# SPK_P.net
KiCad netlist of a schematic drawn in Altium Designer
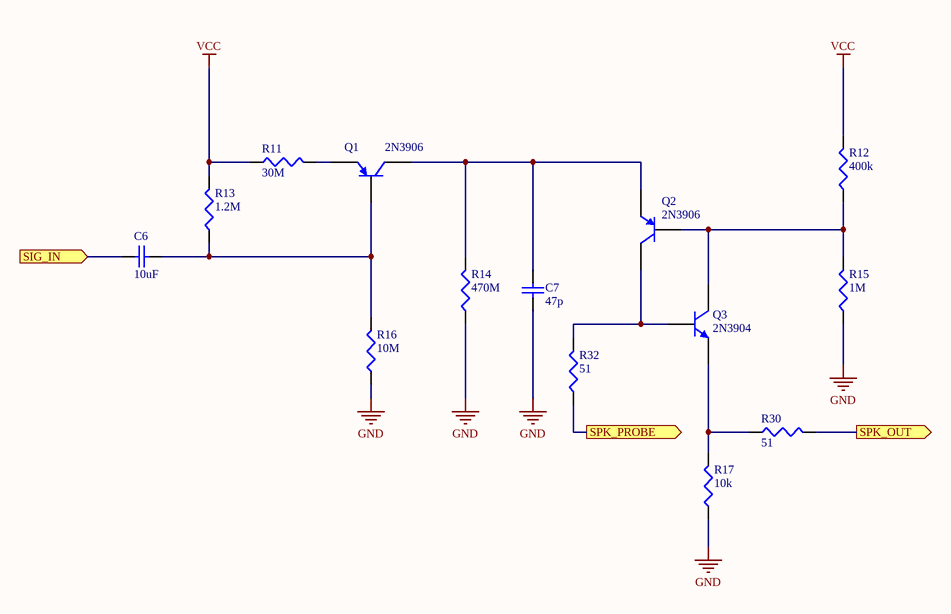
[diagram p0: SPK_P.SchDoc]

(export (version "E")
  (design (tool "Eeschema 10.0.6"))
  (components
    (comp (ref "C6")
      (value "10uF")
      (footprint "SMD-0603")
      (description "Ceramic Capacitor 0603")
      (libsource (lib "LCR") (part "CAP0603"))
    )
    (comp (ref "C7")
      (value "47p")
      (footprint "SMD-0603")
      (description "Ceramic Capacitor 0603")
      (libsource (lib "LCR") (part "CAP0603"))
    )
    (comp (ref "Q1")
      (value "2N3906")
      (footprint "TO-92A")
      (description "PNP General Purpose Amplifier")
      (fields (field (name "PUBLISHER") "Altium Limited"))
      (libsource (lib "Miscellaneous Devices") (part "2N3906"))
    )
    (comp (ref "Q2")
      (value "2N3906")
      (footprint "TO-92A")
      (description "PNP General Purpose Amplifier")
      (fields (field (name "PUBLISHER") "Altium Limited"))
      (libsource (lib "Miscellaneous Devices") (part "2N3906"))
    )
    (comp (ref "Q3")
      (value "2N3904")
      (footprint "TO-92A")
      (description "NPN General Purpose Amplifier")
      (fields (field (name "PUBLISHER") "Altium Limited"))
      (libsource (lib "Miscellaneous Devices") (part "2N3904"))
    )
    (comp (ref "R11")
      (value "30M")
      (footprint "SMD-0603")
      (description "Resistor-0603")
      (libsource (lib "LCR") (part "RES0603"))
    )
    (comp (ref "R12")
      (value "400k")
      (footprint "SMD-0603")
      (description "Resistor-0603")
      (libsource (lib "LCR") (part "RES0603"))
    )
    (comp (ref "R13")
      (value "1.2M")
      (footprint "SMD-0603")
      (description "Resistor-0603")
      (libsource (lib "LCR") (part "RES0603"))
    )
    (comp (ref "R14")
      (value "470M")
      (footprint "SMD-0603")
      (description "Resistor-0603")
      (libsource (lib "LCR") (part "RES0603"))
    )
    (comp (ref "R15")
      (value "1M")
      (footprint "SMD-0603")
      (description "Resistor-0603")
      (libsource (lib "LCR") (part "RES0603"))
    )
    (comp (ref "R16")
      (value "10M")
      (footprint "SMD-0603")
      (description "Resistor-0603")
      (libsource (lib "LCR") (part "RES0603"))
    )
    (comp (ref "R17")
      (value "10k")
      (footprint "SMD-0603")
      (description "Resistor-0603")
      (libsource (lib "LCR") (part "RES0603"))
    )
    (comp (ref "R30")
      (value "51")
      (footprint "SMD-0603")
      (description "Resistor-0603")
      (libsource (lib "LCR") (part "RES0603"))
    )
    (comp (ref "R32")
      (value "51")
      (footprint "SMD-0603")
      (description "Resistor-0603")
      (libsource (lib "LCR") (part "RES0603"))
    )
  )
  (nets
    (net (code "1") (name "/SIG_IN") (class "Default")
      (node (ref "C6") (pin "1") (pinfunction "1_1") (pintype "passive"))
    )
    (net (code "2") (name "/SPK_OUT") (class "Default")
      (node (ref "R30") (pin "2") (pinfunction "2_2") (pintype "passive"))
    )
    (net (code "3") (name "/SPK_PROBE") (class "Default")
      (node (ref "R32") (pin "1") (pinfunction "1_1") (pintype "passive"))
    )
    (net (code "4") (name "GND") (class "Default")
      (node (ref "C7") (pin "1") (pinfunction "1_1") (pintype "passive"))
      (node (ref "R14") (pin "1") (pinfunction "1_1") (pintype "passive"))
      (node (ref "R15") (pin "1") (pinfunction "1_1") (pintype "passive"))
      (node (ref "R16") (pin "1") (pinfunction "1_1") (pintype "passive"))
      (node (ref "R17") (pin "1") (pinfunction "1_1") (pintype "passive"))
    )
    (net (code "5") (name "Net-(Q1-B)") (class "Default")
      (node (ref "C6") (pin "2") (pinfunction "2_2") (pintype "passive"))
      (node (ref "Q1") (pin "2") (pinfunction "B_2") (pintype "passive"))
      (node (ref "R13") (pin "1") (pinfunction "1_1") (pintype "passive"))
      (node (ref "R16") (pin "2") (pinfunction "2_2") (pintype "passive"))
    )
    (net (code "6") (name "Net-(Q1-C)") (class "Default")
      (node (ref "C7") (pin "2") (pinfunction "2_2") (pintype "passive"))
      (node (ref "Q1") (pin "3") (pinfunction "C_3") (pintype "passive"))
      (node (ref "Q2") (pin "1") (pinfunction "E_1") (pintype "passive"))
      (node (ref "R14") (pin "2") (pinfunction "2_2") (pintype "passive"))
    )
    (net (code "7") (name "Net-(Q1-E)") (class "Default")
      (node (ref "Q1") (pin "1") (pinfunction "E_1") (pintype "passive"))
      (node (ref "R11") (pin "2") (pinfunction "2_2") (pintype "passive"))
    )
    (net (code "8") (name "Net-(Q2-B)") (class "Default")
      (node (ref "Q2") (pin "2") (pinfunction "B_2") (pintype "passive"))
      (node (ref "Q3") (pin "3") (pinfunction "C_3") (pintype "passive"))
      (node (ref "R12") (pin "1") (pinfunction "1_1") (pintype "passive"))
      (node (ref "R15") (pin "2") (pinfunction "2_2") (pintype "passive"))
    )
    (net (code "9") (name "Net-(Q2-C)") (class "Default")
      (node (ref "Q2") (pin "3") (pinfunction "C_3") (pintype "passive"))
      (node (ref "Q3") (pin "2") (pinfunction "B_2") (pintype "passive"))
      (node (ref "R32") (pin "2") (pinfunction "2_2") (pintype "passive"))
    )
    (net (code "10") (name "Net-(Q3-E)") (class "Default")
      (node (ref "Q3") (pin "1") (pinfunction "E_1") (pintype "passive"))
      (node (ref "R17") (pin "2") (pinfunction "2_2") (pintype "passive"))
      (node (ref "R30") (pin "1") (pinfunction "1_1") (pintype "passive"))
    )
    (net (code "11") (name "VCC") (class "Default")
      (node (ref "R11") (pin "1") (pinfunction "1_1") (pintype "passive"))
      (node (ref "R12") (pin "2") (pinfunction "2_2") (pintype "passive"))
      (node (ref "R13") (pin "2") (pinfunction "2_2") (pintype "passive"))
    )
  )
)
